# SmartRock_EC.net
KiCad netlist of a schematic drawn in EAGLE
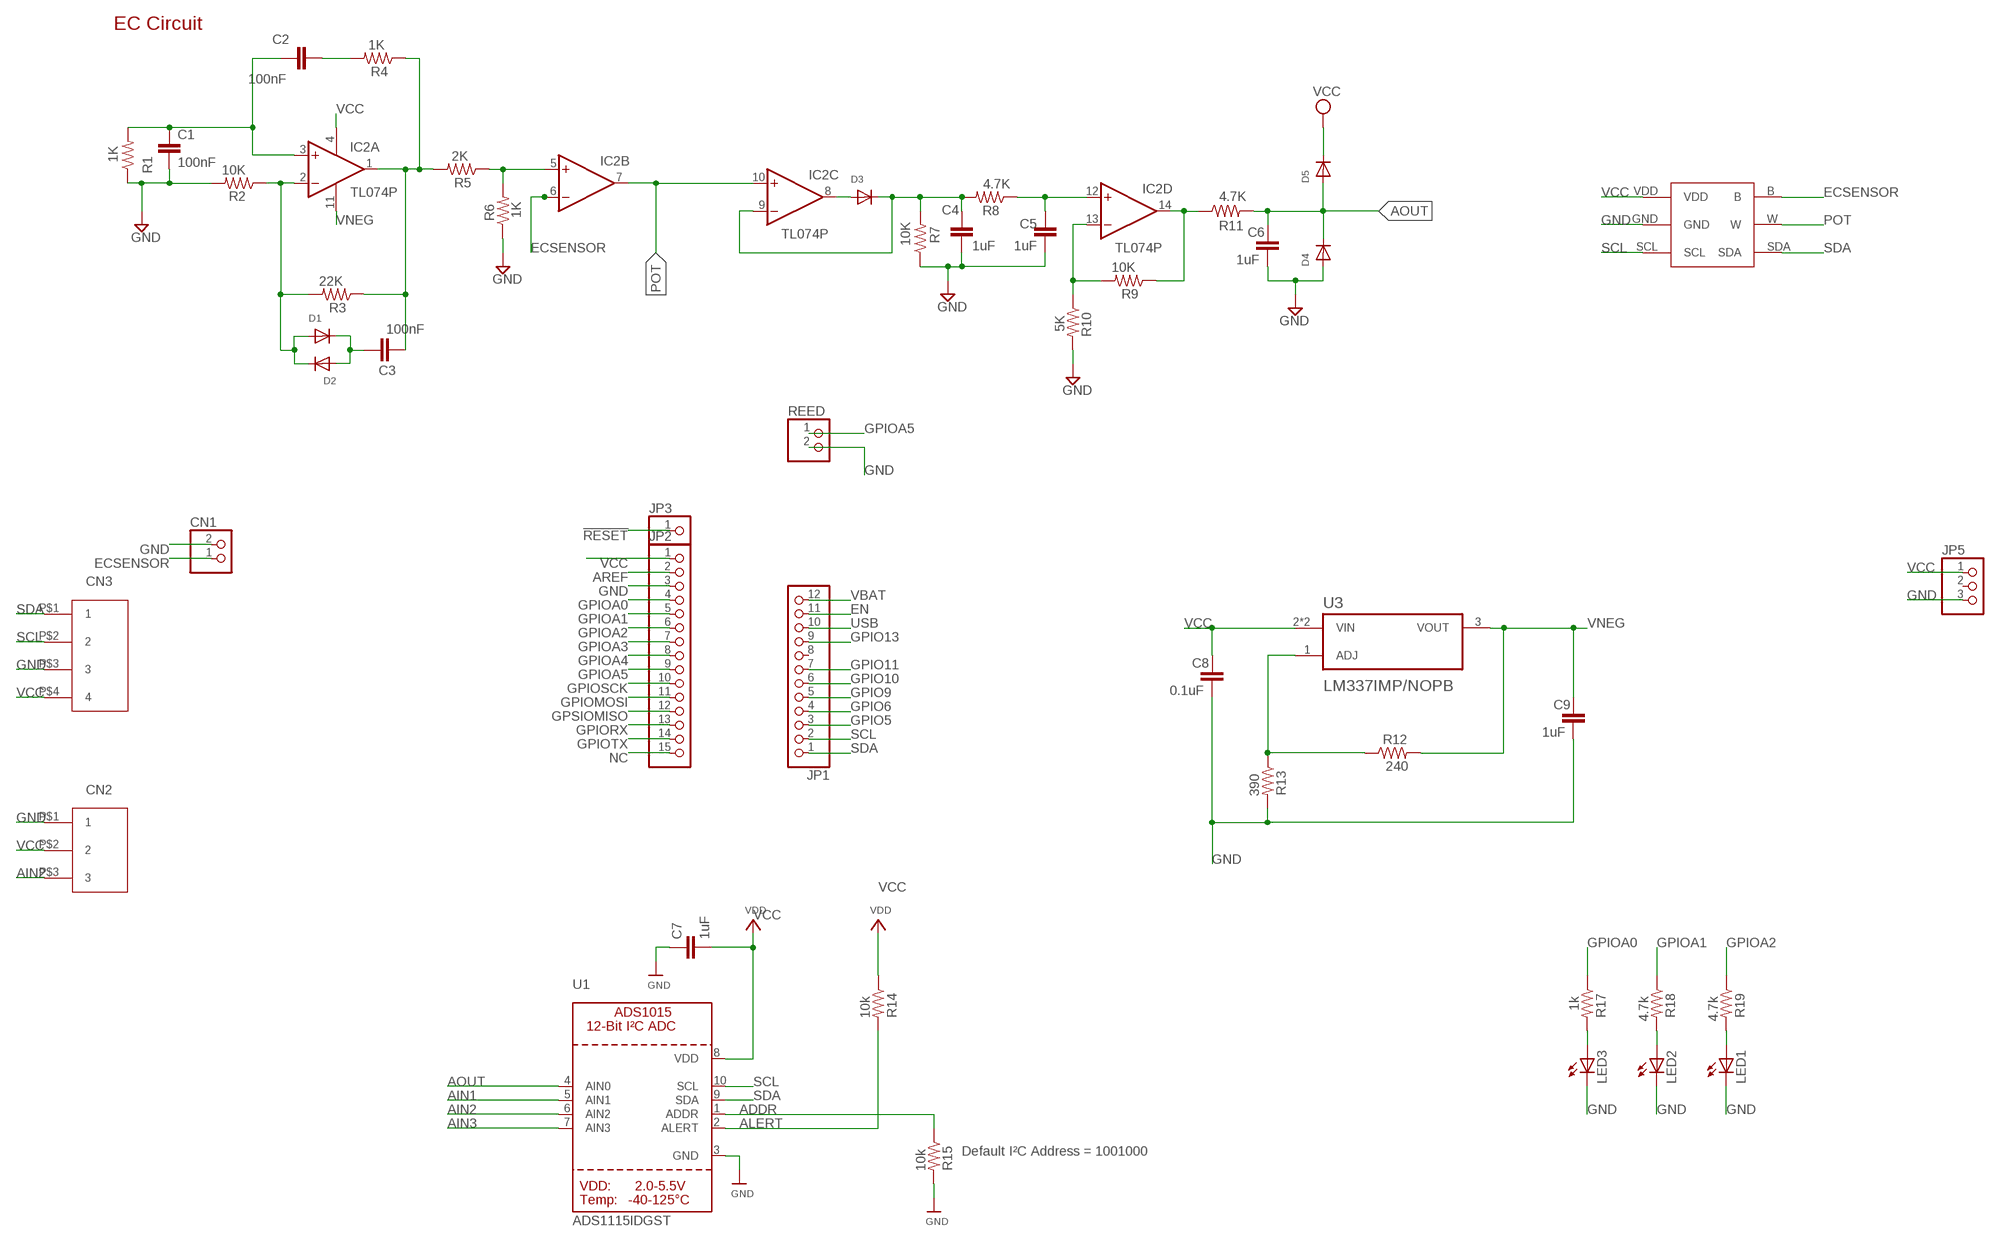
[diagram p0: schematic, sheet 1]

(export (version "E")
  (design (tool "Eeschema 10.0.6"))
  (components
    (comp (ref "C1")
      (value "100nF")
      (footprint "eagle-import:C1206")
      (libsource (lib "eagle-import") (part "C-EUC1206"))
    )
    (comp (ref "C2")
      (value "100nF")
      (footprint "eagle-import:C1206")
      (libsource (lib "eagle-import") (part "C-EUC1206"))
    )
    (comp (ref "C3")
      (value "100nF")
      (footprint "eagle-import:C1206")
      (libsource (lib "eagle-import") (part "C-EUC1206"))
    )
    (comp (ref "C4")
      (value "1uF")
      (footprint "eagle-import:C1206")
      (libsource (lib "eagle-import") (part "C-EUC1206"))
    )
    (comp (ref "C5")
      (value "1uF")
      (footprint "eagle-import:C1206")
      (libsource (lib "eagle-import") (part "C-EUC1206"))
    )
    (comp (ref "C6")
      (value "1uF")
      (footprint "eagle-import:C1206")
      (libsource (lib "eagle-import") (part "C-EUC1206"))
    )
    (comp (ref "C7")
      (value "1uF")
      (footprint "eagle-import:C1206")
      (libsource (lib "eagle-import") (part "C-EUC1206"))
    )
    (comp (ref "C8")
      (value "0.1uF")
      (footprint "eagle-import:C1206")
      (libsource (lib "eagle-import") (part "C-EUC1206"))
    )
    (comp (ref "C9")
      (value "1uF")
      (footprint "eagle-import:C1206")
      (libsource (lib "eagle-import") (part "C-EUC1206"))
    )
    (comp (ref "CN1")
      (value "JST_2PIN-THM")
      (footprint "eagle-import:JST-PH-2-THM")
      (libsource (lib "eagle-import") (part "JST_2PIN-THM"))
    )
    (comp (ref "D1")
      (value "DIODEDO-1N4148")
      (footprint "eagle-import:DO-1N4148")
      (libsource (lib "eagle-import") (part "DIODEDO-1N4148"))
    )
    (comp (ref "D2")
      (value "DIODEDO-1N4148")
      (footprint "eagle-import:DO-1N4148")
      (libsource (lib "eagle-import") (part "DIODEDO-1N4148"))
    )
    (comp (ref "D3")
      (value "DIODEDO-1N4148")
      (footprint "eagle-import:DO-1N4148")
      (libsource (lib "eagle-import") (part "DIODEDO-1N4148"))
    )
    (comp (ref "D4")
      (value "DIODEDO-1N4148")
      (footprint "eagle-import:DO-1N4148")
      (libsource (lib "eagle-import") (part "DIODEDO-1N4148"))
    )
    (comp (ref "D5")
      (value "DIODEDO-1N4148")
      (footprint "eagle-import:DO-1N4148")
      (libsource (lib "eagle-import") (part "DIODEDO-1N4148"))
    )
    (comp (ref "IC2")
      (value "TL074P")
      (footprint "eagle-import:DIL14")
      (libsource (lib "eagle-import") (part "TL074P"))
    )
    (comp (ref "JP1")
      (value "PINHD-1X12-CB")
      (footprint "eagle-import:1X12-CB")
      (libsource (lib "eagle-import") (part "PINHD-1X12-CB"))
    )
    (comp (ref "JP2")
      (value "PINHD-1X15-CB")
      (footprint "eagle-import:1X15-CB")
      (libsource (lib "eagle-import") (part "PINHD-1X15-CB"))
    )
    (comp (ref "JP3")
      (value "PINHD-1X1CB")
      (footprint "eagle-import:1X01-CLEANBIG")
      (libsource (lib "eagle-import") (part "PINHD-1X1CB"))
    )
    (comp (ref "JP5")
      (value "PINHD-1X3CB")
      (footprint "eagle-import:1X03-CLEANBIG")
      (libsource (lib "eagle-import") (part "PINHD-1X3CB"))
    )
    (comp (ref "LED1")
      (value "LEDSMT1206")
      (footprint "eagle-import:1206")
      (libsource (lib "eagle-import") (part "LEDSMT1206"))
    )
    (comp (ref "LED2")
      (value "LEDSMT1206")
      (footprint "eagle-import:1206")
      (libsource (lib "eagle-import") (part "LEDSMT1206"))
    )
    (comp (ref "LED3")
      (value "LEDSMT1206")
      (footprint "eagle-import:1206")
      (libsource (lib "eagle-import") (part "LEDSMT1206"))
    )
    (comp (ref "R1")
      (value "1K")
      (footprint "eagle-import:R1206")
      (libsource (lib "eagle-import") (part "R-US_R1206"))
    )
    (comp (ref "R2")
      (value "10K")
      (footprint "eagle-import:R1206")
      (libsource (lib "eagle-import") (part "R-US_R1206"))
    )
    (comp (ref "R3")
      (value "22K")
      (footprint "eagle-import:R1206")
      (libsource (lib "eagle-import") (part "R-US_R1206"))
    )
    (comp (ref "R4")
      (value "1K")
      (footprint "eagle-import:R1206")
      (libsource (lib "eagle-import") (part "R-US_R1206"))
    )
    (comp (ref "R5")
      (value "2K")
      (footprint "eagle-import:R1206")
      (libsource (lib "eagle-import") (part "R-US_R1206"))
    )
    (comp (ref "R6")
      (value "1K")
      (footprint "eagle-import:R1206")
      (libsource (lib "eagle-import") (part "R-US_R1206"))
    )
    (comp (ref "R7")
      (value "10K")
      (footprint "eagle-import:R1206")
      (libsource (lib "eagle-import") (part "R-US_R1206"))
    )
    (comp (ref "R8")
      (value "4.7K")
      (footprint "eagle-import:R1206")
      (libsource (lib "eagle-import") (part "R-US_R1206"))
    )
    (comp (ref "R9")
      (value "10K")
      (footprint "eagle-import:R1206")
      (libsource (lib "eagle-import") (part "R-US_R1206"))
    )
    (comp (ref "R10")
      (value "5K")
      (footprint "eagle-import:R1206")
      (libsource (lib "eagle-import") (part "R-US_R1206"))
    )
    (comp (ref "R11")
      (value "4.7K")
      (footprint "eagle-import:R1206")
      (libsource (lib "eagle-import") (part "R-US_R1206"))
    )
    (comp (ref "R12")
      (value "240")
      (footprint "eagle-import:R1206")
      (libsource (lib "eagle-import") (part "R-US_R1206"))
    )
    (comp (ref "R13")
      (value "390")
      (footprint "eagle-import:R1206")
      (libsource (lib "eagle-import") (part "R-US_R1206"))
    )
    (comp (ref "R14")
      (value "10k")
      (footprint "eagle-import:R1206")
      (libsource (lib "eagle-import") (part "R-US_R1206"))
    )
    (comp (ref "R15")
      (value "10k")
      (footprint "eagle-import:R1206")
      (libsource (lib "eagle-import") (part "R-US_R1206"))
    )
    (comp (ref "R17")
      (value "1k")
      (footprint "eagle-import:R1206")
      (libsource (lib "eagle-import") (part "R-US_R1206"))
    )
    (comp (ref "R18")
      (value "4.7k")
      (footprint "eagle-import:R1206")
      (libsource (lib "eagle-import") (part "R-US_R1206"))
    )
    (comp (ref "R19")
      (value "4.7k")
      (footprint "eagle-import:R1206")
      (libsource (lib "eagle-import") (part "R-US_R1206"))
    )
    (comp (ref "REED")
      (value "PINHD-1X2")
      (footprint "eagle-import:1X02")
      (libsource (lib "eagle-import") (part "PINHD-1X2"))
    )
    (comp (ref "U$1")
      (value "AD5246")
      (footprint "eagle-import:AD5246")
      (libsource (lib "eagle-import") (part "AD5246"))
    )
    (comp (ref "U$7")
      (value "JST_4PIN_2MM")
      (footprint "eagle-import:JST_4PIN_2MM")
      (libsource (lib "eagle-import") (part "JST_4PIN_2MM"))
    )
    (comp (ref "U$9")
      (value "JST_3PIN_2MM")
      (footprint "eagle-import:JST_3PIN_2MM")
      (libsource (lib "eagle-import") (part "JST_3PIN_2MM"))
    )
    (comp (ref "U1")
      (value "ADS1115IDGST")
      (footprint "eagle-import:MSOP10")
      (libsource (lib "eagle-import") (part "ADC_ADS1015"))
    )
    (comp (ref "U3")
      (value "LM337IMP/NOPB")
      (footprint "eagle-import:SOT230P700X180-4N")
      (fields
        (field (name "DIGI-KEY_PART_NUMBER") "LM337IMPCT-ND")
        (field (name "MF") "Texas Instruments")
        (field (name "MP") "LM337IMP")
      )
      (libsource (lib "eagle-import") (part "LM337IMP/NOPB"))
    )
  )
  (nets
    (net (code "1") (name "/ADDR") (class "Default")
      (node (ref "R15") (pin "1") (pinfunction "1_1") (pintype "passive"))
      (node (ref "U1") (pin "1") (pinfunction "ADDR_1") (pintype "bidirectional"))
    )
    (net (code "2") (name "/AIN1") (class "Default")
      (node (ref "U1") (pin "5") (pinfunction "AIN1_5") (pintype "bidirectional"))
    )
    (net (code "3") (name "/AIN2") (class "Default")
      (node (ref "U$9") (pin "P$3") (pinfunction "3_P$3") (pintype "bidirectional"))
      (node (ref "U1") (pin "6") (pinfunction "AIN2_6") (pintype "bidirectional"))
    )
    (net (code "4") (name "/AIN3") (class "Default")
      (node (ref "U1") (pin "7") (pinfunction "AIN3_7") (pintype "bidirectional"))
    )
    (net (code "5") (name "/ALERT") (class "Default")
      (node (ref "R14") (pin "2") (pinfunction "2_2") (pintype "passive"))
      (node (ref "U1") (pin "2") (pinfunction "ALERT_2") (pintype "bidirectional"))
    )
    (net (code "6") (name "/AREF") (class "Default")
      (node (ref "JP2") (pin "2") (pinfunction "2_2") (pintype "passive"))
    )
    (net (code "7") (name "/ECSENSOR") (class "Default")
      (node (ref "CN1") (pin "1") (pinfunction "2_1") (pintype "passive"))
      (node (ref "IC2") (pin "6") (pinfunction "-IN_6") (pintype "input"))
      (node (ref "U$1") (pin "B") (pinfunction "B_B") (pintype "bidirectional"))
    )
    (net (code "8") (name "/EN") (class "Default")
      (node (ref "JP1") (pin "11") (pinfunction "11_11") (pintype "passive"))
    )
    (net (code "9") (name "/GPIO5") (class "Default")
      (node (ref "JP1") (pin "3") (pinfunction "3_3") (pintype "passive"))
    )
    (net (code "10") (name "/GPIO6") (class "Default")
      (node (ref "JP1") (pin "4") (pinfunction "4_4") (pintype "passive"))
    )
    (net (code "11") (name "/GPIO9") (class "Default")
      (node (ref "JP1") (pin "5") (pinfunction "5_5") (pintype "passive"))
    )
    (net (code "12") (name "/GPIO10") (class "Default")
      (node (ref "JP1") (pin "6") (pinfunction "6_6") (pintype "passive"))
    )
    (net (code "13") (name "/GPIO11") (class "Default")
      (node (ref "JP1") (pin "7") (pinfunction "7_7") (pintype "passive"))
    )
    (net (code "14") (name "/GPIO13") (class "Default")
      (node (ref "JP1") (pin "9") (pinfunction "9_9") (pintype "passive"))
    )
    (net (code "15") (name "/GPIOA0") (class "Default")
      (node (ref "JP2") (pin "4") (pinfunction "4_4") (pintype "passive"))
      (node (ref "R17") (pin "1") (pinfunction "1_1") (pintype "passive"))
    )
    (net (code "16") (name "/GPIOA1") (class "Default")
      (node (ref "JP2") (pin "5") (pinfunction "5_5") (pintype "passive"))
      (node (ref "R18") (pin "1") (pinfunction "1_1") (pintype "passive"))
    )
    (net (code "17") (name "/GPIOA2") (class "Default")
      (node (ref "JP2") (pin "6") (pinfunction "6_6") (pintype "passive"))
      (node (ref "R19") (pin "1") (pinfunction "1_1") (pintype "passive"))
    )
    (net (code "18") (name "/GPIOA3") (class "Default")
      (node (ref "JP2") (pin "7") (pinfunction "7_7") (pintype "passive"))
    )
    (net (code "19") (name "/GPIOA4") (class "Default")
      (node (ref "JP2") (pin "8") (pinfunction "8_8") (pintype "passive"))
    )
    (net (code "20") (name "/GPIOA5") (class "Default")
      (node (ref "JP2") (pin "9") (pinfunction "9_9") (pintype "passive"))
      (node (ref "REED") (pin "1") (pinfunction "1_1") (pintype "passive"))
    )
    (net (code "21") (name "/GPIOMOSI") (class "Default")
      (node (ref "JP2") (pin "11") (pinfunction "11_11") (pintype "passive"))
    )
    (net (code "22") (name "/GPIORX") (class "Default")
      (node (ref "JP2") (pin "13") (pinfunction "13_13") (pintype "passive"))
    )
    (net (code "23") (name "/GPIOSCK") (class "Default")
      (node (ref "JP2") (pin "10") (pinfunction "10_10") (pintype "passive"))
    )
    (net (code "24") (name "/GPIOTX") (class "Default")
      (node (ref "JP2") (pin "14") (pinfunction "14_14") (pintype "passive"))
    )
    (net (code "25") (name "/GPSIOMISO") (class "Default")
      (node (ref "JP2") (pin "12") (pinfunction "12_12") (pintype "passive"))
    )
    (net (code "26") (name "/NC") (class "Default")
      (node (ref "JP2") (pin "15") (pinfunction "15_15") (pintype "passive"))
    )
    (net (code "27") (name "/SCL") (class "Default")
      (node (ref "JP1") (pin "2") (pinfunction "2_2") (pintype "passive"))
      (node (ref "U$1") (pin "SCL") (pinfunction "SCL_SCL") (pintype "bidirectional"))
      (node (ref "U$7") (pin "P$2") (pinfunction "2_P$2") (pintype "bidirectional"))
      (node (ref "U1") (pin "10") (pinfunction "SCL_10") (pintype "bidirectional"))
    )
    (net (code "28") (name "/SDA") (class "Default")
      (node (ref "JP1") (pin "1") (pinfunction "1_1") (pintype "passive"))
      (node (ref "U$1") (pin "SDA") (pinfunction "SDA_SDA") (pintype "bidirectional"))
      (node (ref "U$7") (pin "P$1") (pinfunction "1_P$1") (pintype "bidirectional"))
      (node (ref "U1") (pin "9") (pinfunction "SDA_9") (pintype "bidirectional"))
    )
    (net (code "29") (name "/USB") (class "Default")
      (node (ref "JP1") (pin "10") (pinfunction "10_10") (pintype "passive"))
    )
    (net (code "30") (name "/VBAT") (class "Default")
      (node (ref "JP1") (pin "12") (pinfunction "12_12") (pintype "passive"))
    )
    (net (code "31") (name "/VNEG") (class "Default")
      (node (ref "C9") (pin "2") (pinfunction "2_2") (pintype "passive"))
      (node (ref "IC2") (pin "11") (pinfunction "V-_11") (pintype "power_in"))
      (node (ref "R12") (pin "2") (pinfunction "2_2") (pintype "passive"))
      (node (ref "U3") (pin "3") (pinfunction "VOUT_3") (pintype "output"))
    )
    (net (code "32") (name "/~{RESET}") (class "Default")
      (node (ref "JP3") (pin "1") (pinfunction "1_1") (pintype "passive"))
    )
    (net (code "33") (name "AOUT") (class "Default")
      (node (ref "C6") (pin "2") (pinfunction "2_2") (pintype "passive"))
      (node (ref "D4") (pin "C") (pinfunction "C_C") (pintype "passive"))
      (node (ref "D5") (pin "A") (pinfunction "A_A") (pintype "passive"))
      (node (ref "R11") (pin "2") (pinfunction "2_2") (pintype "passive"))
      (node (ref "U1") (pin "4") (pinfunction "AIN0_4") (pintype "bidirectional"))
    )
    (net (code "34") (name "GND") (class "Default")
      (node (ref "C1") (pin "2") (pinfunction "2_2") (pintype "passive"))
      (node (ref "C4") (pin "1") (pinfunction "1_1") (pintype "passive"))
      (node (ref "C5") (pin "1") (pinfunction "1_1") (pintype "passive"))
      (node (ref "C6") (pin "1") (pinfunction "1_1") (pintype "passive"))
      (node (ref "C7") (pin "1") (pinfunction "1_1") (pintype "passive"))
      (node (ref "C8") (pin "1") (pinfunction "1_1") (pintype "passive"))
      (node (ref "C9") (pin "1") (pinfunction "1_1") (pintype "passive"))
      (node (ref "CN1") (pin "2") (pinfunction "1_2") (pintype "passive"))
      (node (ref "D4") (pin "A") (pinfunction "A_A") (pintype "passive"))
      (node (ref "JP2") (pin "3") (pinfunction "3_3") (pintype "passive"))
      (node (ref "JP5") (pin "3") (pinfunction "3_3") (pintype "passive"))
      (node (ref "LED1") (pin "C") (pinfunction "C_C") (pintype "passive"))
      (node (ref "LED2") (pin "C") (pinfunction "C_C") (pintype "passive"))
      (node (ref "LED3") (pin "C") (pinfunction "C_C") (pintype "passive"))
      (node (ref "R1") (pin "1") (pinfunction "1_1") (pintype "passive"))
      (node (ref "R10") (pin "2") (pinfunction "2_2") (pintype "passive"))
      (node (ref "R13") (pin "2") (pinfunction "2_2") (pintype "passive"))
      (node (ref "R15") (pin "2") (pinfunction "2_2") (pintype "passive"))
      (node (ref "R2") (pin "2") (pinfunction "2_2") (pintype "passive"))
      (node (ref "R6") (pin "1") (pinfunction "1_1") (pintype "passive"))
      (node (ref "R7") (pin "1") (pinfunction "1_1") (pintype "passive"))
      (node (ref "REED") (pin "2") (pinfunction "2_2") (pintype "passive"))
      (node (ref "U$1") (pin "GND") (pinfunction "GND_GND") (pintype "bidirectional"))
      (node (ref "U$7") (pin "P$3") (pinfunction "3_P$3") (pintype "bidirectional"))
      (node (ref "U$9") (pin "P$1") (pinfunction "1_P$1") (pintype "bidirectional"))
      (node (ref "U1") (pin "3") (pinfunction "GND_3") (pintype "bidirectional"))
    )
    (net (code "35") (name "Net-(C2-Pad2)") (class "Default")
      (node (ref "C2") (pin "2") (pinfunction "2_2") (pintype "passive"))
      (node (ref "R4") (pin "2") (pinfunction "2_2") (pintype "passive"))
    )
    (net (code "36") (name "Net-(C3-Pad1)") (class "Default")
      (node (ref "C3") (pin "1") (pinfunction "1_1") (pintype "passive"))
      (node (ref "D1") (pin "C") (pinfunction "C_C") (pintype "passive"))
      (node (ref "D2") (pin "A") (pinfunction "A_A") (pintype "passive"))
    )
    (net (code "37") (name "Net-(IC2A-+IN)") (class "Default")
      (node (ref "C1") (pin "1") (pinfunction "1_1") (pintype "passive"))
      (node (ref "C2") (pin "1") (pinfunction "1_1") (pintype "passive"))
      (node (ref "IC2") (pin "3") (pinfunction "+IN_3") (pintype "input"))
      (node (ref "R1") (pin "2") (pinfunction "2_2") (pintype "passive"))
    )
    (net (code "38") (name "Net-(IC2A--IN)") (class "Default")
      (node (ref "D1") (pin "A") (pinfunction "A_A") (pintype "passive"))
      (node (ref "D2") (pin "C") (pinfunction "C_C") (pintype "passive"))
      (node (ref "IC2") (pin "2") (pinfunction "-IN_2") (pintype "input"))
      (node (ref "R2") (pin "1") (pinfunction "1_1") (pintype "passive"))
      (node (ref "R3") (pin "2") (pinfunction "2_2") (pintype "passive"))
    )
    (net (code "39") (name "Net-(IC2A-OUT)") (class "Default")
      (node (ref "C3") (pin "2") (pinfunction "2_2") (pintype "passive"))
      (node (ref "IC2") (pin "1") (pinfunction "OUT_1") (pintype "output"))
      (node (ref "R3") (pin "1") (pinfunction "1_1") (pintype "passive"))
      (node (ref "R4") (pin "1") (pinfunction "1_1") (pintype "passive"))
      (node (ref "R5") (pin "2") (pinfunction "2_2") (pintype "passive"))
    )
    (net (code "40") (name "Net-(IC2B-+IN)") (class "Default")
      (node (ref "IC2") (pin "5") (pinfunction "+IN_5") (pintype "input"))
      (node (ref "R5") (pin "1") (pinfunction "1_1") (pintype "passive"))
      (node (ref "R6") (pin "2") (pinfunction "2_2") (pintype "passive"))
    )
    (net (code "41") (name "Net-(IC2C--IN)") (class "Default")
      (node (ref "C4") (pin "2") (pinfunction "2_2") (pintype "passive"))
      (node (ref "D3") (pin "C") (pinfunction "C_C") (pintype "passive"))
      (node (ref "IC2") (pin "9") (pinfunction "-IN_9") (pintype "input"))
      (node (ref "R7") (pin "2") (pinfunction "2_2") (pintype "passive"))
      (node (ref "R8") (pin "2") (pinfunction "2_2") (pintype "passive"))
    )
    (net (code "42") (name "Net-(IC2C-OUT)") (class "Default")
      (node (ref "D3") (pin "A") (pinfunction "A_A") (pintype "passive"))
      (node (ref "IC2") (pin "8") (pinfunction "OUT_8") (pintype "output"))
    )
    (net (code "43") (name "Net-(IC2D-+IN)") (class "Default")
      (node (ref "C5") (pin "2") (pinfunction "2_2") (pintype "passive"))
      (node (ref "IC2") (pin "12") (pinfunction "+IN_12") (pintype "input"))
      (node (ref "R8") (pin "1") (pinfunction "1_1") (pintype "passive"))
    )
    (net (code "44") (name "Net-(IC2D--IN)") (class "Default")
      (node (ref "IC2") (pin "13") (pinfunction "-IN_13") (pintype "input"))
      (node (ref "R10") (pin "1") (pinfunction "1_1") (pintype "passive"))
      (node (ref "R9") (pin "2") (pinfunction "2_2") (pintype "passive"))
    )
    (net (code "45") (name "Net-(IC2D-OUT)") (class "Default")
      (node (ref "IC2") (pin "14") (pinfunction "OUT_14") (pintype "output"))
      (node (ref "R11") (pin "1") (pinfunction "1_1") (pintype "passive"))
      (node (ref "R9") (pin "1") (pinfunction "1_1") (pintype "passive"))
    )
    (net (code "46") (name "Net-(LED1-PadA)") (class "Default")
      (node (ref "LED1") (pin "A") (pinfunction "A_A") (pintype "passive"))
      (node (ref "R19") (pin "2") (pinfunction "2_2") (pintype "passive"))
    )
    (net (code "47") (name "Net-(LED2-PadA)") (class "Default")
      (node (ref "LED2") (pin "A") (pinfunction "A_A") (pintype "passive"))
      (node (ref "R18") (pin "2") (pinfunction "2_2") (pintype "passive"))
    )
    (net (code "48") (name "Net-(LED3-PadA)") (class "Default")
      (node (ref "LED3") (pin "A") (pinfunction "A_A") (pintype "passive"))
      (node (ref "R17") (pin "2") (pinfunction "2_2") (pintype "passive"))
    )
    (net (code "49") (name "Net-(U3-ADJ)") (class "Default")
      (node (ref "R12") (pin "1") (pinfunction "1_1") (pintype "passive"))
      (node (ref "R13") (pin "1") (pinfunction "1_1") (pintype "passive"))
      (node (ref "U3") (pin "1") (pinfunction "ADJ_1") (pintype "bidirectional"))
    )
    (net (code "50") (name "POT") (class "Default")
      (node (ref "IC2") (pin "10") (pinfunction "+IN_10") (pintype "input"))
      (node (ref "IC2") (pin "7") (pinfunction "OUT_7") (pintype "output"))
      (node (ref "U$1") (pin "W") (pinfunction "W_W") (pintype "bidirectional"))
    )
    (net (code "51") (name "VCC") (class "Default")
      (node (ref "C7") (pin "2") (pinfunction "2_2") (pintype "passive"))
      (node (ref "C8") (pin "2") (pinfunction "2_2") (pintype "passive"))
      (node (ref "D5") (pin "C") (pinfunction "C_C") (pintype "passive"))
      (node (ref "IC2") (pin "4") (pinfunction "V+_4") (pintype "power_in"))
      (node (ref "JP2") (pin "1") (pinfunction "1_1") (pintype "passive"))
      (node (ref "JP5") (pin "1") (pinfunction "1_1") (pintype "passive"))
      (node (ref "R14") (pin "1") (pinfunction "1_1") (pintype "passive"))
      (node (ref "U$1") (pin "VDD") (pinfunction "VDD_VDD") (pintype "bidirectional"))
      (node (ref "U$7") (pin "P$4") (pinfunction "4_P$4") (pintype "bidirectional"))
      (node (ref "U$9") (pin "P$2") (pinfunction "2_P$2") (pintype "bidirectional"))
      (node (ref "U1") (pin "8") (pinfunction "VDD_8") (pintype "bidirectional"))
      (node (ref "U3") (pin "2") (pinfunction "VIN_2") (pintype "input"))
      (node (ref "U3") (pin "4") (pinfunction "VIN_4") (pintype "input"))
    )
    (net (code "52") (name "unconnected-(JP1-Pad8)") (class "Default")
      (node (ref "JP1") (pin "8") (pinfunction "8_8") (pintype "passive"))
    )
    (net (code "53") (name "unconnected-(JP5-Pad2)") (class "Default")
      (node (ref "JP5") (pin "2") (pinfunction "2_2") (pintype "passive"))
    )
  )
)
